# resisdelit.net
KiCad netlist of a schematic drawn in EAGLE
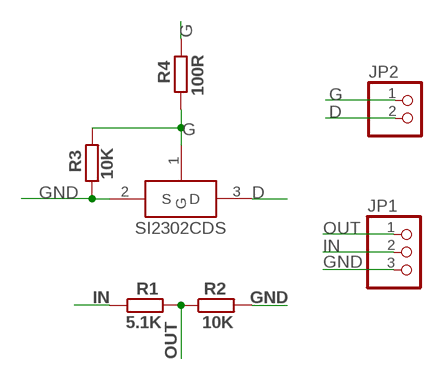
[diagram p0: schematic, sheet 1]

(export (version "E")
  (design (tool "Eeschema 10.0.6"))
  (components
    (comp (ref "JP1")
      (value "PINHD-1X3")
      (footprint "eagle-import:1X03")
      (libsource (lib "eagle-import") (part "PINHD-1X3"))
    )
    (comp (ref "JP2")
      (value "PINHD-1X2")
      (footprint "eagle-import:1X02")
      (libsource (lib "eagle-import") (part "PINHD-1X2"))
    )
    (comp (ref "R1")
      (value "5.1K")
      (footprint "eagle-import:R0603")
      (libsource (lib "eagle-import") (part "R-EU_R0603"))
    )
    (comp (ref "R2")
      (value "10K")
      (footprint "eagle-import:R0603")
      (libsource (lib "eagle-import") (part "R-EU_R0603"))
    )
    (comp (ref "R3")
      (value "10K")
      (footprint "eagle-import:R0603")
      (libsource (lib "eagle-import") (part "R-EU_R0603"))
    )
    (comp (ref "R4")
      (value "100R")
      (footprint "eagle-import:R0603")
      (libsource (lib "eagle-import") (part "R-EU_R0603"))
    )
    (comp (ref "SI2300A")
      (value "SI2302CDS")
      (footprint "eagle-import:SOT23-3")
      (libsource (lib "eagle-import") (part "SI2302CDS"))
    )
  )
  (nets
    (net (code "1") (name "/D") (class "Default")
      (node (ref "JP2") (pin "2") (pinfunction "2_2") (pintype "passive"))
      (node (ref "SI2300A") (pin "3") (pinfunction "D_3") (pintype "bidirectional"))
    )
    (net (code "2") (name "/G") (class "Default")
      (node (ref "JP2") (pin "1") (pinfunction "1_1") (pintype "passive"))
      (node (ref "R3") (pin "2") (pinfunction "2_2") (pintype "passive"))
      (node (ref "R4") (pin "1") (pinfunction "1_1") (pintype "passive"))
      (node (ref "R4") (pin "2") (pinfunction "2_2") (pintype "passive"))
      (node (ref "SI2300A") (pin "1") (pinfunction "G_1") (pintype "bidirectional"))
    )
    (net (code "3") (name "/GND") (class "Default")
      (node (ref "JP1") (pin "3") (pinfunction "3_3") (pintype "passive"))
      (node (ref "R2") (pin "2") (pinfunction "2_2") (pintype "passive"))
      (node (ref "R3") (pin "1") (pinfunction "1_1") (pintype "passive"))
      (node (ref "SI2300A") (pin "2") (pinfunction "S_2") (pintype "bidirectional"))
    )
    (net (code "4") (name "/IN") (class "Default")
      (node (ref "JP1") (pin "2") (pinfunction "2_2") (pintype "passive"))
      (node (ref "R1") (pin "1") (pinfunction "1_1") (pintype "passive"))
    )
    (net (code "5") (name "/OUT") (class "Default")
      (node (ref "JP1") (pin "1") (pinfunction "1_1") (pintype "passive"))
      (node (ref "R1") (pin "2") (pinfunction "2_2") (pintype "passive"))
      (node (ref "R2") (pin "1") (pinfunction "1_1") (pintype "passive"))
    )
  )
)
